# 2_ETH.net
KiCad netlist of a schematic drawn in Altium Designer
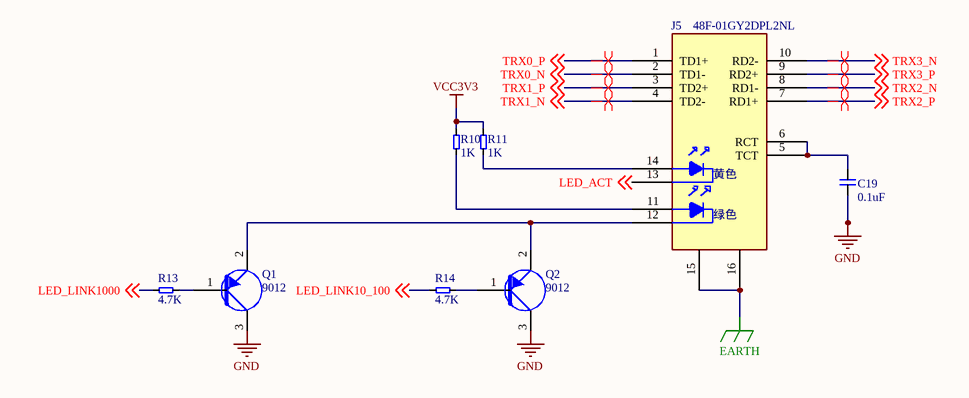
[diagram p0: 2.ETH.SchDoc]

(export (version "E")
  (design (tool "Eeschema 10.0.6"))
  (components
    (comp (ref "C19")
      (value "0.1uF")
      (footprint "0603C")
      (description "电容")
      (libsource (lib "LDT-SCH") (part "电容"))
    )
    (comp (ref "J5")
      (value "48F-01GY2DPL2NL")
      (footprint "RJ45C-48F-01GY2DPL2NL")
      (libsource (lib "LDT-SCH") (part "48F-01GY2DPL2NL"))
    )
    (comp (ref "Q1") (value "9012") (footprint "SOT-23-PMOS") (libsource (lib "LDT-SCH") (part "9012")))
    (comp (ref "Q2") (value "9012") (footprint "SOT-23-PMOS") (libsource (lib "LDT-SCH") (part "9012")))
    (comp (ref "R10")
      (value "1K")
      (footprint "0603R")
      (description "电阻")
      (libsource (lib "LDT-SCH") (part "电阻"))
    )
    (comp (ref "R11")
      (value "1K")
      (footprint "0603R")
      (description "电阻")
      (libsource (lib "LDT-SCH") (part "电阻"))
    )
    (comp (ref "R13")
      (value "4.7K")
      (footprint "0603R")
      (description "电阻")
      (libsource (lib "LDT-SCH") (part "电阻"))
    )
    (comp (ref "R14")
      (value "4.7K")
      (footprint "0603R")
      (description "电阻")
      (libsource (lib "LDT-SCH") (part "电阻"))
    )
  )
  (nets
    (net (code "1") (name "EARTH") (class "Default")
      (node (ref "J5") (pin "15") (pinfunction "15_15") (pintype "passive"))
      (node (ref "J5") (pin "16") (pinfunction "16_16") (pintype "passive"))
    )
    (net (code "2") (name "GND") (class "Default")
      (node (ref "C19") (pin "2") (pintype "passive"))
      (node (ref "Q1") (pin "3") (pintype "passive"))
      (node (ref "Q2") (pin "3") (pintype "passive"))
    )
    (net (code "3") (name "LED_ACT") (class "Default")
      (node (ref "J5") (pin "13") (pinfunction "13_13") (pintype "passive"))
    )
    (net (code "4") (name "LED_LINK10_100") (class "Default")
      (node (ref "R14") (pin "2") (pintype "passive"))
    )
    (net (code "5") (name "LED_LINK1000") (class "Default") (node (ref "R13") (pin "2") (pintype "passive")))
    (net (code "6") (name "Net-(J5-Pad11)") (class "Default")
      (node (ref "J5") (pin "11") (pinfunction "11_11") (pintype "passive"))
      (node (ref "R10") (pin "1") (pintype "passive"))
    )
    (net (code "7") (name "Net-(J5-Pad12)") (class "Default")
      (node (ref "J5") (pin "12") (pinfunction "12_12") (pintype "passive"))
      (node (ref "Q1") (pin "2") (pintype "passive"))
      (node (ref "Q2") (pin "2") (pintype "passive"))
    )
    (net (code "8") (name "Net-(J5-Pad14)") (class "Default")
      (node (ref "J5") (pin "14") (pinfunction "14_14") (pintype "passive"))
      (node (ref "R11") (pin "1") (pintype "passive"))
    )
    (net (code "9") (name "Net-(J5-RCT)") (class "Default")
      (node (ref "C19") (pin "1") (pintype "passive"))
      (node (ref "J5") (pin "5") (pinfunction "TCT_5") (pintype "passive"))
      (node (ref "J5") (pin "6") (pinfunction "RCT_6") (pintype "passive"))
    )
    (net (code "10") (name "Net-(Q1-Pad1)") (class "Default")
      (node (ref "Q1") (pin "1") (pintype "passive"))
      (node (ref "R13") (pin "1") (pintype "passive"))
    )
    (net (code "11") (name "Net-(Q2-Pad1)") (class "Default")
      (node (ref "Q2") (pin "1") (pintype "passive"))
      (node (ref "R14") (pin "1") (pintype "passive"))
    )
    (net (code "12") (name "TRX0_N") (class "Default")
      (node (ref "J5") (pin "2") (pinfunction "TD1-_2") (pintype "passive"))
    )
    (net (code "13") (name "TRX0_P") (class "Default")
      (node (ref "J5") (pin "1") (pinfunction "TD1+_1") (pintype "passive"))
    )
    (net (code "14") (name "TRX1_N") (class "Default")
      (node (ref "J5") (pin "4") (pinfunction "TD2-_4") (pintype "passive"))
    )
    (net (code "15") (name "TRX1_P") (class "Default")
      (node (ref "J5") (pin "3") (pinfunction "TD2+_3") (pintype "passive"))
    )
    (net (code "16") (name "TRX2_N") (class "Default")
      (node (ref "J5") (pin "8") (pinfunction "RD1-_8") (pintype "passive"))
    )
    (net (code "17") (name "TRX2_P") (class "Default")
      (node (ref "J5") (pin "7") (pinfunction "RD1+_7") (pintype "passive"))
    )
    (net (code "18") (name "TRX3_N") (class "Default")
      (node (ref "J5") (pin "10") (pinfunction "RD2-_10") (pintype "passive"))
    )
    (net (code "19") (name "TRX3_P") (class "Default")
      (node (ref "J5") (pin "9") (pinfunction "RD2+_9") (pintype "passive"))
    )
    (net (code "20") (name "VCC3V3") (class "Default")
      (node (ref "R10") (pin "2") (pintype "passive"))
      (node (ref "R11") (pin "2") (pintype "passive"))
    )
  )
)
